# attiny2312.net
KiCad netlist of a schematic drawn in EAGLE
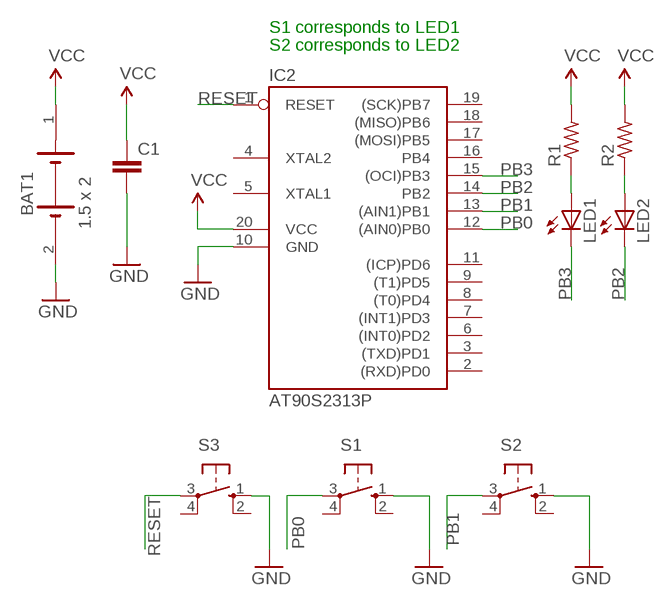
[diagram p0: schematic, sheet 1]

(export (version "E")
  (design (tool "Eeschema 10.0.6"))
  (components
    (comp (ref "BAT1")
      (value "1.5 x 2")
      (footprint "eagle-import:RELIMATE")
      (libsource (lib "eagle-import") (part "1.5X2BATTERYRELIMATE"))
    )
    (comp (ref "C1")
      (value "C2.5/2")
      (footprint "eagle-import:C2.5-2")
      (libsource (lib "eagle-import") (part "C2.5/2"))
    )
    (comp (ref "IC2")
      (value "AT90S2313P")
      (footprint "eagle-import:DIL20")
      (libsource (lib "eagle-import") (part "AT90S2313P"))
    )
    (comp (ref "LED1")
      (value "LED3MM")
      (footprint "eagle-import:LED3MM")
      (libsource (lib "eagle-import") (part "LED3MM"))
    )
    (comp (ref "LED2")
      (value "LED3MM")
      (footprint "eagle-import:LED3MM")
      (libsource (lib "eagle-import") (part "LED3MM"))
    )
    (comp (ref "R1")
      (value "R-US_0207/10")
      (footprint "eagle-import:0207_10")
      (libsource (lib "eagle-import") (part "R-US_0207/10"))
    )
    (comp (ref "R2")
      (value "R-US_0207/10")
      (footprint "eagle-import:0207_10")
      (libsource (lib "eagle-import") (part "R-US_0207/10"))
    )
    (comp (ref "S1")
      (value "10-XX")
      (footprint "eagle-import:B3F-10XX")
      (libsource (lib "eagle-import") (part "10-XX"))
    )
    (comp (ref "S2")
      (value "10-XX")
      (footprint "eagle-import:B3F-10XX")
      (libsource (lib "eagle-import") (part "10-XX"))
    )
    (comp (ref "S3")
      (value "10-XX")
      (footprint "eagle-import:B3F-10XX")
      (libsource (lib "eagle-import") (part "10-XX"))
    )
  )
  (nets
    (net (code "1") (name "/PB0") (class "Default")
      (node (ref "IC2") (pin "12") (pinfunction "(AIN0)PB0_12") (pintype "bidirectional"))
      (node (ref "S1") (pin "3") (pinfunction "P_3") (pintype "passive"))
    )
    (net (code "2") (name "/PB1") (class "Default")
      (node (ref "IC2") (pin "13") (pinfunction "(AIN1)PB1_13") (pintype "bidirectional"))
      (node (ref "S2") (pin "3") (pinfunction "P_3") (pintype "passive"))
    )
    (net (code "3") (name "/PB2") (class "Default")
      (node (ref "IC2") (pin "14") (pinfunction "PB2_14") (pintype "bidirectional"))
      (node (ref "LED2") (pin "K") (pinfunction "C_K") (pintype "passive"))
    )
    (net (code "4") (name "/PB3") (class "Default")
      (node (ref "IC2") (pin "15") (pinfunction "(OCI)PB3_15") (pintype "bidirectional"))
      (node (ref "LED1") (pin "K") (pinfunction "C_K") (pintype "passive"))
    )
    (net (code "5") (name "/RESET") (class "Default")
      (node (ref "IC2") (pin "1") (pinfunction "RESET_1") (pintype "bidirectional"))
      (node (ref "S3") (pin "3") (pinfunction "P_3") (pintype "passive"))
    )
    (net (code "6") (name "GND") (class "Default")
      (node (ref "BAT1") (pin "2") (pinfunction "2_2") (pintype "power_in"))
      (node (ref "C1") (pin "2") (pinfunction "2_2") (pintype "passive"))
      (node (ref "IC2") (pin "10") (pinfunction "GND_10") (pintype "power_in"))
      (node (ref "S1") (pin "1") (pinfunction "S_1") (pintype "passive"))
      (node (ref "S2") (pin "1") (pinfunction "S_1") (pintype "passive"))
      (node (ref "S3") (pin "1") (pinfunction "S_1") (pintype "passive"))
    )
    (net (code "7") (name "Net-(LED1-PadA)") (class "Default")
      (node (ref "LED1") (pin "A") (pinfunction "A_A") (pintype "passive"))
      (node (ref "R1") (pin "1") (pinfunction "1_1") (pintype "passive"))
    )
    (net (code "8") (name "Net-(LED2-PadA)") (class "Default")
      (node (ref "LED2") (pin "A") (pinfunction "A_A") (pintype "passive"))
      (node (ref "R2") (pin "1") (pinfunction "1_1") (pintype "passive"))
    )
    (net (code "9") (name "VCC") (class "Default")
      (node (ref "BAT1") (pin "1") (pinfunction "1_1") (pintype "power_in"))
      (node (ref "C1") (pin "1") (pinfunction "1_1") (pintype "passive"))
      (node (ref "IC2") (pin "20") (pinfunction "VCC_20") (pintype "power_in"))
      (node (ref "R1") (pin "2") (pinfunction "2_2") (pintype "passive"))
      (node (ref "R2") (pin "2") (pinfunction "2_2") (pintype "passive"))
    )
    (net (code "10") (name "unconnected-(IC2-(ICP)PD6-Pad11)") (class "Default")
      (node (ref "IC2") (pin "11") (pinfunction "(ICP)PD6_11") (pintype "bidirectional"))
    )
    (net (code "11") (name "unconnected-(IC2-(INT0)PD2-Pad6)") (class "Default")
      (node (ref "IC2") (pin "6") (pinfunction "(INT0)PD2_6") (pintype "bidirectional"))
    )
    (net (code "12") (name "unconnected-(IC2-(INT1)PD3-Pad7)") (class "Default")
      (node (ref "IC2") (pin "7") (pinfunction "(INT1)PD3_7") (pintype "bidirectional"))
    )
    (net (code "13") (name "unconnected-(IC2-(MISO)PB6-Pad18)") (class "Default")
      (node (ref "IC2") (pin "18") (pinfunction "(MISO)PB6_18") (pintype "bidirectional"))
    )
    (net (code "14") (name "unconnected-(IC2-(MOSI)PB5-Pad17)") (class "Default")
      (node (ref "IC2") (pin "17") (pinfunction "(MOSI)PB5_17") (pintype "bidirectional"))
    )
    (net (code "15") (name "unconnected-(IC2-(RXD)PD0-Pad2)") (class "Default")
      (node (ref "IC2") (pin "2") (pinfunction "(RXD)PD0_2") (pintype "bidirectional"))
    )
    (net (code "16") (name "unconnected-(IC2-(SCK)PB7-Pad19)") (class "Default")
      (node (ref "IC2") (pin "19") (pinfunction "(SCK)PB7_19") (pintype "bidirectional"))
    )
    (net (code "17") (name "unconnected-(IC2-(T0)PD4-Pad8)") (class "Default")
      (node (ref "IC2") (pin "8") (pinfunction "(T0)PD4_8") (pintype "bidirectional"))
    )
    (net (code "18") (name "unconnected-(IC2-(T1)PD5-Pad9)") (class "Default")
      (node (ref "IC2") (pin "9") (pinfunction "(T1)PD5_9") (pintype "bidirectional"))
    )
    (net (code "19") (name "unconnected-(IC2-(TXD)PD1-Pad3)") (class "Default")
      (node (ref "IC2") (pin "3") (pinfunction "(TXD)PD1_3") (pintype "bidirectional"))
    )
    (net (code "20") (name "unconnected-(IC2-PB4-Pad16)") (class "Default")
      (node (ref "IC2") (pin "16") (pinfunction "PB4_16") (pintype "bidirectional"))
    )
    (net (code "21") (name "unconnected-(IC2-XTAL1-Pad5)") (class "Default")
      (node (ref "IC2") (pin "5") (pinfunction "XTAL1_5") (pintype "bidirectional"))
    )
    (net (code "22") (name "unconnected-(IC2-XTAL2-Pad4)") (class "Default")
      (node (ref "IC2") (pin "4") (pinfunction "XTAL2_4") (pintype "bidirectional"))
    )
    (net (code "23") (name "unconnected-(S1-P1-Pad4)") (class "Default")
      (node (ref "S1") (pin "4") (pinfunction "P1_4") (pintype "passive"))
    )
    (net (code "24") (name "unconnected-(S1-S1-Pad2)") (class "Default")
      (node (ref "S1") (pin "2") (pinfunction "S1_2") (pintype "passive"))
    )
    (net (code "25") (name "unconnected-(S2-P1-Pad4)") (class "Default")
      (node (ref "S2") (pin "4") (pinfunction "P1_4") (pintype "passive"))
    )
    (net (code "26") (name "unconnected-(S2-S1-Pad2)") (class "Default")
      (node (ref "S2") (pin "2") (pinfunction "S1_2") (pintype "passive"))
    )
    (net (code "27") (name "unconnected-(S3-P1-Pad4)") (class "Default")
      (node (ref "S3") (pin "4") (pinfunction "P1_4") (pintype "passive"))
    )
    (net (code "28") (name "unconnected-(S3-S1-Pad2)") (class "Default")
      (node (ref "S3") (pin "2") (pinfunction "S1_2") (pintype "passive"))
    )
  )
)
